# h-bridge_v3.net
KiCad netlist of a schematic drawn in EAGLE
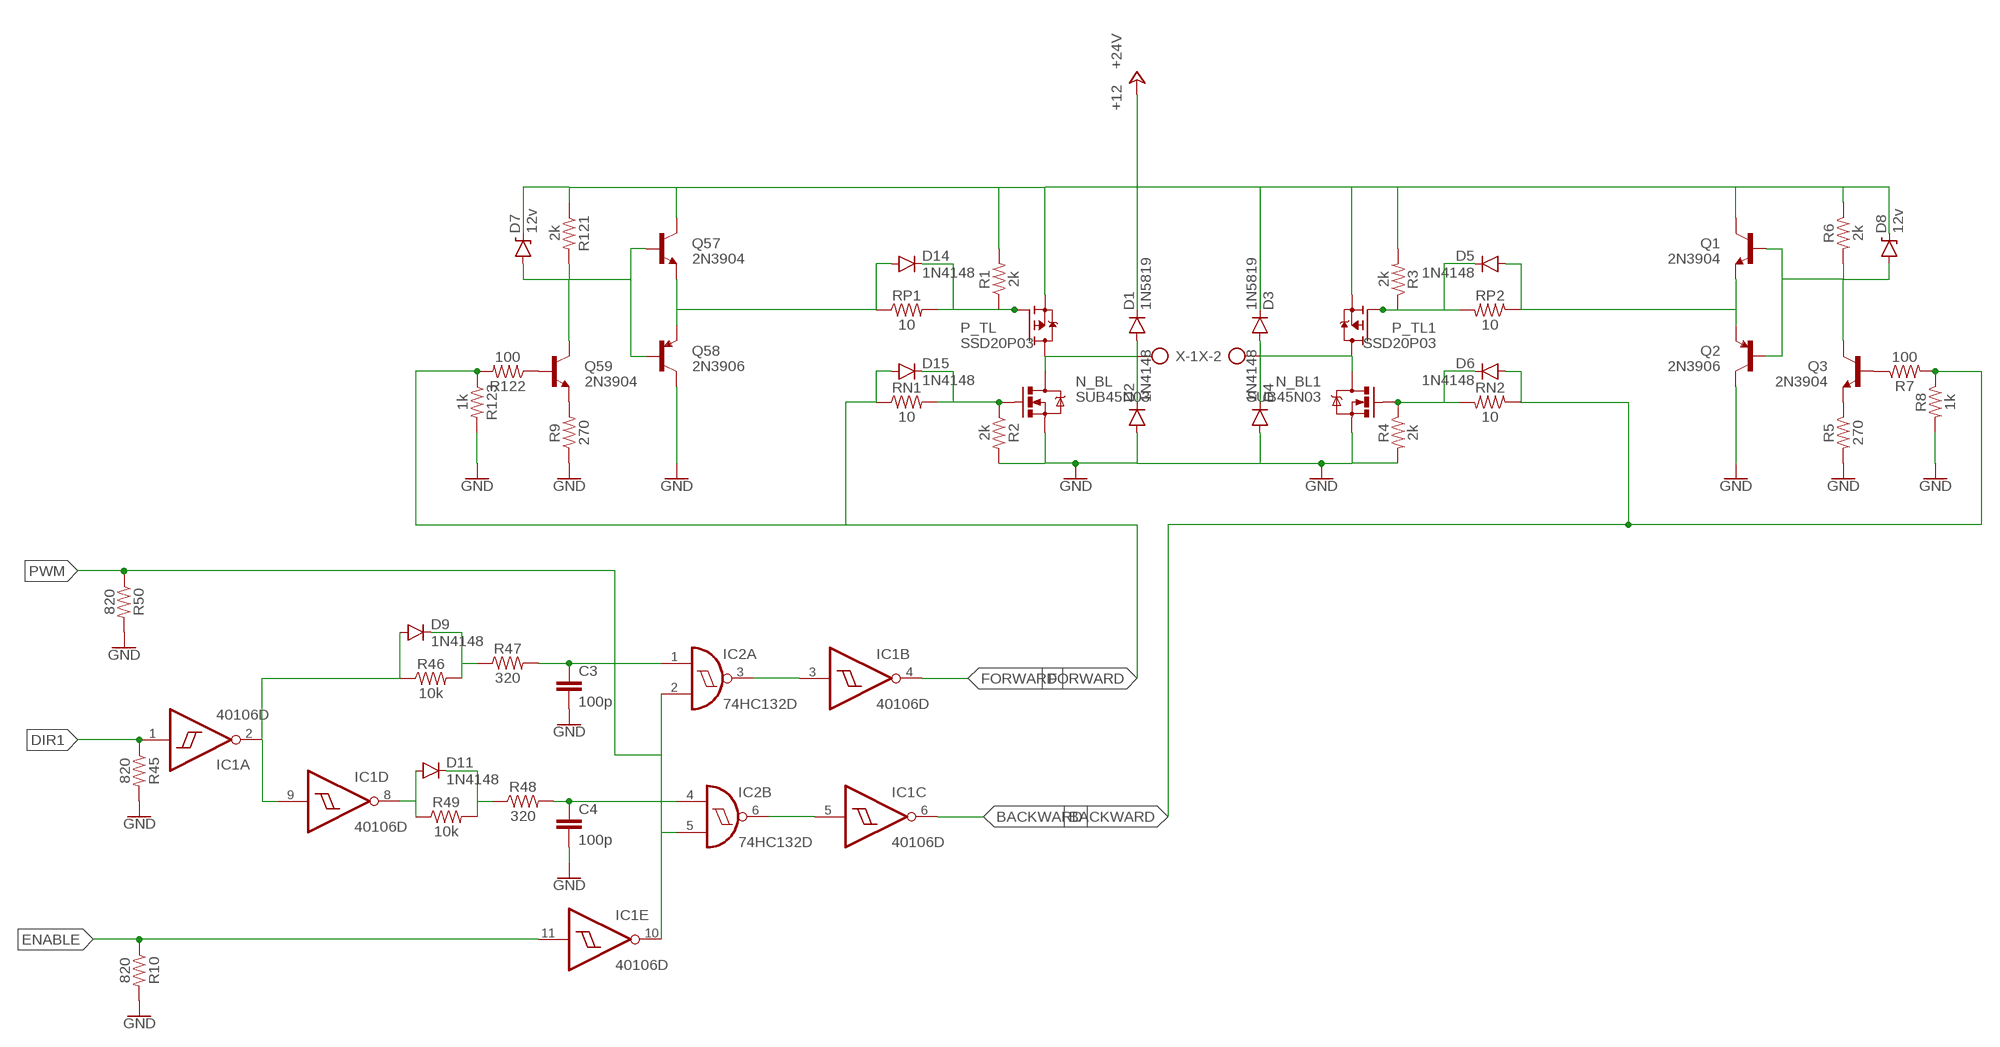
[diagram p0: schematic, sheet 1]

(export (version "E")
  (design (tool "Eeschema 10.0.6"))
  (components
    (comp (ref "C3")
      (value "100p")
      (footprint "eagle-import:0805-CAP")
      (libsource (lib "eagle-import") (part "1.0UF-25V-+80/-20(0805){dblquote}"))
    )
    (comp (ref "C4")
      (value "100p")
      (footprint "eagle-import:0805-CAP")
      (libsource (lib "eagle-import") (part "1.0UF-25V-+80/-20(0805){dblquote}"))
    )
    (comp (ref "D1")
      (value "1N5819")
      (footprint "eagle-import:SOD-123")
      (libsource (lib "eagle-import") (part "DIODESOD123"))
    )
    (comp (ref "D2")
      (value "1N4148")
      (footprint "eagle-import:SOD-123")
      (libsource (lib "eagle-import") (part "DIODESOD123"))
    )
    (comp (ref "D3")
      (value "1N5819")
      (footprint "eagle-import:SOD-123")
      (libsource (lib "eagle-import") (part "DIODESOD123"))
    )
    (comp (ref "D4")
      (value "1N4148")
      (footprint "eagle-import:SOD-123")
      (libsource (lib "eagle-import") (part "DIODESOD123"))
    )
    (comp (ref "D5")
      (value "1N4148")
      (footprint "eagle-import:SOD-123")
      (libsource (lib "eagle-import") (part "DIODESOD123"))
    )
    (comp (ref "D6")
      (value "1N4148")
      (footprint "eagle-import:SOD-123")
      (libsource (lib "eagle-import") (part "DIODESOD123"))
    )
    (comp (ref "D7")
      (value "12v")
      (footprint "eagle-import:SOD-123")
      (libsource (lib "eagle-import") (part "DIODE-ZENER16V"))
    )
    (comp (ref "D8")
      (value "12v")
      (footprint "eagle-import:SOD-123")
      (libsource (lib "eagle-import") (part "DIODE-ZENER16V"))
    )
    (comp (ref "D9")
      (value "1N4148")
      (footprint "eagle-import:SOD-123")
      (libsource (lib "eagle-import") (part "DIODESOD123"))
    )
    (comp (ref "D11")
      (value "1N4148")
      (footprint "eagle-import:SOD-123")
      (libsource (lib "eagle-import") (part "DIODESOD123"))
    )
    (comp (ref "D14")
      (value "1N4148")
      (footprint "eagle-import:SOD-123")
      (libsource (lib "eagle-import") (part "DIODESOD123"))
    )
    (comp (ref "D15")
      (value "1N4148")
      (footprint "eagle-import:SOD-123")
      (libsource (lib "eagle-import") (part "DIODESOD123"))
    )
    (comp (ref "IC1")
      (value "40106D")
      (footprint "eagle-import:SO14")
      (libsource (lib "eagle-import") (part "40106D"))
    )
    (comp (ref "IC2")
      (value "74HC132D")
      (footprint "eagle-import:SO14")
      (libsource (lib "eagle-import") (part "74132DHC"))
    )
    (comp (ref "N_BL")
      (value "SUB45N03")
      (footprint "eagle-import:TO-263_D2PAK")
      (libsource (lib "eagle-import") (part "MOSFET-NCHANNELPSMN7R0"))
    )
    (comp (ref "N_BL1")
      (value "SUB45N03")
      (footprint "eagle-import:TO-263_D2PAK")
      (libsource (lib "eagle-import") (part "MOSFET-NCHANNELPSMN7R0"))
    )
    (comp (ref "P_TL")
      (value "SSD20P03")
      (footprint "eagle-import:TO252")
      (libsource (lib "eagle-import") (part "FDD4141TO252"))
    )
    (comp (ref "P_TL1")
      (value "SSD20P03")
      (footprint "eagle-import:TO252")
      (libsource (lib "eagle-import") (part "FDD4141TO252"))
    )
    (comp (ref "Q1")
      (value "2N3904")
      (footprint "eagle-import:SOT23-3")
      (libsource (lib "eagle-import") (part "TRANSISTOR_NPNMMBT5088"))
    )
    (comp (ref "Q2")
      (value "2N3906")
      (footprint "eagle-import:SOT23-3")
      (libsource (lib "eagle-import") (part "TRANSISTOR_PNPPMBT3906"))
    )
    (comp (ref "Q3")
      (value "2N3904")
      (footprint "eagle-import:SOT23-3")
      (libsource (lib "eagle-import") (part "TRANSISTOR_NPNMMBT5088"))
    )
    (comp (ref "Q57")
      (value "2N3904")
      (footprint "eagle-import:SOT23-3")
      (libsource (lib "eagle-import") (part "TRANSISTOR_NPNMMBT5088"))
    )
    (comp (ref "Q58")
      (value "2N3906")
      (footprint "eagle-import:SOT23-3")
      (libsource (lib "eagle-import") (part "TRANSISTOR_PNPPMBT3906"))
    )
    (comp (ref "Q59")
      (value "2N3904")
      (footprint "eagle-import:SOT23-3")
      (libsource (lib "eagle-import") (part "TRANSISTOR_NPNMMBT5088"))
    )
    (comp (ref "R1")
      (value "2k")
      (footprint "eagle-import:AXIAL-0.3")
      (libsource (lib "eagle-import") (part "RESISTORAXIAL-0.3"))
    )
    (comp (ref "R2")
      (value "2k")
      (footprint "eagle-import:AXIAL-0.3")
      (libsource (lib "eagle-import") (part "RESISTORAXIAL-0.3"))
    )
    (comp (ref "R3")
      (value "2k")
      (footprint "eagle-import:AXIAL-0.3")
      (libsource (lib "eagle-import") (part "RESISTORAXIAL-0.3"))
    )
    (comp (ref "R4")
      (value "2k")
      (footprint "eagle-import:AXIAL-0.3")
      (libsource (lib "eagle-import") (part "RESISTORAXIAL-0.3"))
    )
    (comp (ref "R5")
      (value "270")
      (footprint "eagle-import:AXIAL-0.3")
      (libsource (lib "eagle-import") (part "RESISTORAXIAL-0.3"))
    )
    (comp (ref "R6")
      (value "2k")
      (footprint "eagle-import:AXIAL-0.3")
      (libsource (lib "eagle-import") (part "RESISTORAXIAL-0.3"))
    )
    (comp (ref "R7")
      (value "100")
      (footprint "eagle-import:AXIAL-0.3")
      (libsource (lib "eagle-import") (part "RESISTORAXIAL-0.3"))
    )
    (comp (ref "R8")
      (value "1k")
      (footprint "eagle-import:AXIAL-0.3")
      (libsource (lib "eagle-import") (part "RESISTORAXIAL-0.3"))
    )
    (comp (ref "R9")
      (value "270")
      (footprint "eagle-import:AXIAL-0.3")
      (libsource (lib "eagle-import") (part "RESISTORAXIAL-0.3"))
    )
    (comp (ref "R10")
      (value "820")
      (footprint "eagle-import:AXIAL-0.3")
      (libsource (lib "eagle-import") (part "RESISTORAXIAL-0.3"))
    )
    (comp (ref "R45")
      (value "820")
      (footprint "eagle-import:AXIAL-0.3")
      (libsource (lib "eagle-import") (part "RESISTORAXIAL-0.3"))
    )
    (comp (ref "R46")
      (value "10k")
      (footprint "eagle-import:AXIAL-0.3")
      (libsource (lib "eagle-import") (part "RESISTORAXIAL-0.3"))
    )
    (comp (ref "R47")
      (value "320")
      (footprint "eagle-import:AXIAL-0.3")
      (libsource (lib "eagle-import") (part "RESISTORAXIAL-0.3"))
    )
    (comp (ref "R48")
      (value "320")
      (footprint "eagle-import:AXIAL-0.3")
      (libsource (lib "eagle-import") (part "RESISTORAXIAL-0.3"))
    )
    (comp (ref "R49")
      (value "10k")
      (footprint "eagle-import:AXIAL-0.3")
      (libsource (lib "eagle-import") (part "RESISTORAXIAL-0.3"))
    )
    (comp (ref "R50")
      (value "820")
      (footprint "eagle-import:AXIAL-0.3")
      (libsource (lib "eagle-import") (part "RESISTORAXIAL-0.3"))
    )
    (comp (ref "R121")
      (value "2k")
      (footprint "eagle-import:AXIAL-0.3")
      (libsource (lib "eagle-import") (part "RESISTORAXIAL-0.3"))
    )
    (comp (ref "R122")
      (value "100")
      (footprint "eagle-import:AXIAL-0.3")
      (libsource (lib "eagle-import") (part "RESISTORAXIAL-0.3"))
    )
    (comp (ref "R123")
      (value "1k")
      (footprint "eagle-import:AXIAL-0.3")
      (libsource (lib "eagle-import") (part "RESISTORAXIAL-0.3"))
    )
    (comp (ref "RN1")
      (value "10")
      (footprint "eagle-import:AXIAL-0.3")
      (libsource (lib "eagle-import") (part "RESISTORAXIAL-0.3"))
    )
    (comp (ref "RN2")
      (value "10")
      (footprint "eagle-import:AXIAL-0.3")
      (libsource (lib "eagle-import") (part "RESISTORAXIAL-0.3"))
    )
    (comp (ref "RP1")
      (value "10")
      (footprint "eagle-import:AXIAL-0.3")
      (libsource (lib "eagle-import") (part "RESISTORAXIAL-0.3"))
    )
    (comp (ref "RP2")
      (value "10")
      (footprint "eagle-import:AXIAL-0.3")
      (libsource (lib "eagle-import") (part "RESISTORAXIAL-0.3"))
    )
    (comp (ref "X")
      (value "SMKDSP_1,5/2")
      (footprint "eagle-import:SMKDSP_1,5_2")
      (fields (field (name "MF") "FARNELL") (field (name "MPN") "1733570"))
      (libsource (lib "eagle-import") (part "SMKDSP_1,5/2"))
    )
  )
  (nets
    (net (code "1") (name "+12    +24V") (class "Default")
      (node (ref "D1") (pin "C") (pinfunction "C_C") (pintype "passive"))
      (node (ref "D3") (pin "C") (pinfunction "C_C") (pintype "passive"))
      (node (ref "D7") (pin "C") (pinfunction "C_C") (pintype "passive"))
      (node (ref "D8") (pin "C") (pinfunction "C_C") (pintype "passive"))
      (node (ref "P_TL") (pin "2") (pinfunction "S_2") (pintype "passive"))
      (node (ref "P_TL1") (pin "2") (pinfunction "S_2") (pintype "passive"))
      (node (ref "Q1") (pin "3") (pinfunction "C_3") (pintype "passive"))
      (node (ref "Q57") (pin "3") (pinfunction "C_3") (pintype "passive"))
      (node (ref "R1") (pin "P$2") (pinfunction "2_P$2") (pintype "passive"))
      (node (ref "R121") (pin "P$1") (pinfunction "1_P$1") (pintype "passive"))
      (node (ref "R3") (pin "P$2") (pinfunction "2_P$2") (pintype "passive"))
      (node (ref "R6") (pin "P$1") (pinfunction "1_P$1") (pintype "passive"))
    )
    (net (code "2") (name "BACKWARD") (class "Default")
      (node (ref "D6") (pin "A") (pinfunction "A_A") (pintype "passive"))
      (node (ref "IC1") (pin "6") (pinfunction "O_6") (pintype "output"))
      (node (ref "R7") (pin "P$2") (pinfunction "2_P$2") (pintype "passive"))
      (node (ref "R8") (pin "P$1") (pinfunction "1_P$1") (pintype "passive"))
      (node (ref "RN2") (pin "P$1") (pinfunction "1_P$1") (pintype "passive"))
    )
    (net (code "3") (name "DIR1") (class "Default")
      (node (ref "IC1") (pin "1") (pinfunction "I_1") (pintype "input"))
      (node (ref "R45") (pin "P$1") (pinfunction "1_P$1") (pintype "passive"))
    )
    (net (code "4") (name "ENABLE") (class "Default")
      (node (ref "IC1") (pin "11") (pinfunction "I_11") (pintype "input"))
      (node (ref "R10") (pin "P$1") (pinfunction "1_P$1") (pintype "passive"))
    )
    (net (code "5") (name "FORWARD") (class "Default")
      (node (ref "D15") (pin "A") (pinfunction "A_A") (pintype "passive"))
      (node (ref "IC1") (pin "4") (pinfunction "O_4") (pintype "output"))
      (node (ref "R122") (pin "P$2") (pinfunction "2_P$2") (pintype "passive"))
      (node (ref "R123") (pin "P$1") (pinfunction "1_P$1") (pintype "passive"))
      (node (ref "RN1") (pin "P$1") (pinfunction "1_P$1") (pintype "passive"))
    )
    (net (code "6") (name "GND") (class "Default")
      (node (ref "C3") (pin "2") (pinfunction "2_2") (pintype "passive"))
      (node (ref "C4") (pin "2") (pinfunction "2_2") (pintype "passive"))
      (node (ref "D2") (pin "A") (pinfunction "A_A") (pintype "passive"))
      (node (ref "D4") (pin "A") (pinfunction "A_A") (pintype "passive"))
      (node (ref "N_BL") (pin "3") (pinfunction "S_3") (pintype "passive"))
      (node (ref "N_BL1") (pin "3") (pinfunction "S_3") (pintype "passive"))
      (node (ref "Q2") (pin "3") (pinfunction "C_3") (pintype "passive"))
      (node (ref "Q58") (pin "3") (pinfunction "C_3") (pintype "passive"))
      (node (ref "R10") (pin "P$2") (pinfunction "2_P$2") (pintype "passive"))
      (node (ref "R123") (pin "P$2") (pinfunction "2_P$2") (pintype "passive"))
      (node (ref "R2") (pin "P$2") (pinfunction "2_P$2") (pintype "passive"))
      (node (ref "R4") (pin "P$2") (pinfunction "2_P$2") (pintype "passive"))
      (node (ref "R45") (pin "P$2") (pinfunction "2_P$2") (pintype "passive"))
      (node (ref "R5") (pin "P$2") (pinfunction "2_P$2") (pintype "passive"))
      (node (ref "R50") (pin "P$2") (pinfunction "2_P$2") (pintype "passive"))
      (node (ref "R8") (pin "P$2") (pinfunction "2_P$2") (pintype "passive"))
      (node (ref "R9") (pin "P$1") (pinfunction "1_P$1") (pintype "passive"))
    )
    (net (code "7") (name "Net-(IC1A-O)") (class "Default")
      (node (ref "D9") (pin "A") (pinfunction "A_A") (pintype "passive"))
      (node (ref "IC1") (pin "2") (pinfunction "O_2") (pintype "output"))
      (node (ref "IC1") (pin "9") (pinfunction "I_9") (pintype "input"))
      (node (ref "R46") (pin "P$1") (pinfunction "1_P$1") (pintype "passive"))
    )
    (net (code "8") (name "Net-(IC1B-I)") (class "Default")
      (node (ref "IC1") (pin "3") (pinfunction "I_3") (pintype "input"))
      (node (ref "IC2") (pin "3") (pinfunction "O_3") (pintype "output"))
    )
    (net (code "9") (name "Net-(IC1C-I)") (class "Default")
      (node (ref "IC1") (pin "5") (pinfunction "I_5") (pintype "input"))
      (node (ref "IC2") (pin "6") (pinfunction "O_6") (pintype "output"))
    )
    (net (code "10") (name "Net-(IC1D-O)") (class "Default")
      (node (ref "D11") (pin "A") (pinfunction "A_A") (pintype "passive"))
      (node (ref "IC1") (pin "8") (pinfunction "O_8") (pintype "output"))
      (node (ref "R49") (pin "P$1") (pinfunction "1_P$1") (pintype "passive"))
    )
    (net (code "11") (name "Net-(IC2A-I0)") (class "Default")
      (node (ref "C3") (pin "1") (pinfunction "1_1") (pintype "passive"))
      (node (ref "IC2") (pin "1") (pinfunction "I0_1") (pintype "input"))
      (node (ref "R47") (pin "P$2") (pinfunction "2_P$2") (pintype "passive"))
    )
    (net (code "12") (name "Net-(IC2B-I0)") (class "Default")
      (node (ref "C4") (pin "1") (pinfunction "1_1") (pintype "passive"))
      (node (ref "IC2") (pin "4") (pinfunction "I0_4") (pintype "input"))
      (node (ref "R48") (pin "P$2") (pinfunction "2_P$2") (pintype "passive"))
    )
    (net (code "13") (name "Net-(N_BL-D)") (class "Default")
      (node (ref "D1") (pin "A") (pinfunction "A_A") (pintype "passive"))
      (node (ref "D2") (pin "C") (pinfunction "C_C") (pintype "passive"))
      (node (ref "N_BL") (pin "2") (pinfunction "D_2") (pintype "passive"))
      (node (ref "P_TL") (pin "3") (pinfunction "D_3") (pintype "passive"))
      (node (ref "X") (pin "1") (pinfunction "KL_1") (pintype "passive"))
    )
    (net (code "14") (name "Net-(N_BL-G)") (class "Default")
      (node (ref "D15") (pin "C") (pinfunction "C_C") (pintype "passive"))
      (node (ref "N_BL") (pin "1") (pinfunction "G_1") (pintype "passive"))
      (node (ref "R2") (pin "P$1") (pinfunction "1_P$1") (pintype "passive"))
      (node (ref "RN1") (pin "P$2") (pinfunction "2_P$2") (pintype "passive"))
    )
    (net (code "15") (name "Net-(N_BL1-D)") (class "Default")
      (node (ref "D3") (pin "A") (pinfunction "A_A") (pintype "passive"))
      (node (ref "D4") (pin "C") (pinfunction "C_C") (pintype "passive"))
      (node (ref "N_BL1") (pin "2") (pinfunction "D_2") (pintype "passive"))
      (node (ref "P_TL1") (pin "3") (pinfunction "D_3") (pintype "passive"))
      (node (ref "X") (pin "2") (pinfunction "KL_2") (pintype "passive"))
    )
    (net (code "16") (name "Net-(N_BL1-G)") (class "Default")
      (node (ref "D6") (pin "C") (pinfunction "C_C") (pintype "passive"))
      (node (ref "N_BL1") (pin "1") (pinfunction "G_1") (pintype "passive"))
      (node (ref "R4") (pin "P$1") (pinfunction "1_P$1") (pintype "passive"))
      (node (ref "RN2") (pin "P$2") (pinfunction "2_P$2") (pintype "passive"))
    )
    (net (code "17") (name "Net-(P_TL-G)") (class "Default")
      (node (ref "D14") (pin "C") (pinfunction "C_C") (pintype "passive"))
      (node (ref "P_TL") (pin "1") (pinfunction "G_1") (pintype "passive"))
      (node (ref "R1") (pin "P$1") (pinfunction "1_P$1") (pintype "passive"))
      (node (ref "RP1") (pin "P$2") (pinfunction "2_P$2") (pintype "passive"))
    )
    (net (code "18") (name "Net-(P_TL1-G)") (class "Default")
      (node (ref "D5") (pin "C") (pinfunction "C_C") (pintype "passive"))
      (node (ref "P_TL1") (pin "1") (pinfunction "G_1") (pintype "passive"))
      (node (ref "R3") (pin "P$1") (pinfunction "1_P$1") (pintype "passive"))
      (node (ref "RP2") (pin "P$2") (pinfunction "2_P$2") (pintype "passive"))
    )
    (net (code "19") (name "Net-(Q1-B)") (class "Default")
      (node (ref "D8") (pin "A") (pinfunction "A_A") (pintype "passive"))
      (node (ref "Q1") (pin "1") (pinfunction "B_1") (pintype "passive"))
      (node (ref "Q2") (pin "1") (pinfunction "B_1") (pintype "passive"))
      (node (ref "Q3") (pin "3") (pinfunction "C_3") (pintype "passive"))
      (node (ref "R6") (pin "P$2") (pinfunction "2_P$2") (pintype "passive"))
    )
    (net (code "20") (name "Net-(Q1-E)") (class "Default")
      (node (ref "D5") (pin "A") (pinfunction "A_A") (pintype "passive"))
      (node (ref "Q1") (pin "2") (pinfunction "E_2") (pintype "passive"))
      (node (ref "Q2") (pin "2") (pinfunction "E_2") (pintype "passive"))
      (node (ref "RP2") (pin "P$1") (pinfunction "1_P$1") (pintype "passive"))
    )
    (net (code "21") (name "Net-(Q3-B)") (class "Default")
      (node (ref "Q3") (pin "1") (pinfunction "B_1") (pintype "passive"))
      (node (ref "R7") (pin "P$1") (pinfunction "1_P$1") (pintype "passive"))
    )
    (net (code "22") (name "Net-(Q3-E)") (class "Default")
      (node (ref "Q3") (pin "2") (pinfunction "E_2") (pintype "passive"))
      (node (ref "R5") (pin "P$1") (pinfunction "1_P$1") (pintype "passive"))
    )
    (net (code "23") (name "Net-(Q57-B)") (class "Default")
      (node (ref "D7") (pin "A") (pinfunction "A_A") (pintype "passive"))
      (node (ref "Q57") (pin "1") (pinfunction "B_1") (pintype "passive"))
      (node (ref "Q58") (pin "1") (pinfunction "B_1") (pintype "passive"))
      (node (ref "Q59") (pin "3") (pinfunction "C_3") (pintype "passive"))
      (node (ref "R121") (pin "P$2") (pinfunction "2_P$2") (pintype "passive"))
    )
    (net (code "24") (name "Net-(Q57-E)") (class "Default")
      (node (ref "D14") (pin "A") (pinfunction "A_A") (pintype "passive"))
      (node (ref "Q57") (pin "2") (pinfunction "E_2") (pintype "passive"))
      (node (ref "Q58") (pin "2") (pinfunction "E_2") (pintype "passive"))
      (node (ref "RP1") (pin "P$1") (pinfunction "1_P$1") (pintype "passive"))
    )
    (net (code "25") (name "Net-(Q59-B)") (class "Default")
      (node (ref "Q59") (pin "1") (pinfunction "B_1") (pintype "passive"))
      (node (ref "R122") (pin "P$1") (pinfunction "1_P$1") (pintype "passive"))
    )
    (net (code "26") (name "Net-(Q59-E)") (class "Default")
      (node (ref "Q59") (pin "2") (pinfunction "E_2") (pintype "passive"))
      (node (ref "R9") (pin "P$2") (pinfunction "2_P$2") (pintype "passive"))
    )
    (net (code "27") (name "Net-(R46-2)") (class "Default")
      (node (ref "D9") (pin "C") (pinfunction "C_C") (pintype "passive"))
      (node (ref "R46") (pin "P$2") (pinfunction "2_P$2") (pintype "passive"))
      (node (ref "R47") (pin "P$1") (pinfunction "1_P$1") (pintype "passive"))
    )
    (net (code "28") (name "Net-(R48-1)") (class "Default")
      (node (ref "D11") (pin "C") (pinfunction "C_C") (pintype "passive"))
      (node (ref "R48") (pin "P$1") (pinfunction "1_P$1") (pintype "passive"))
      (node (ref "R49") (pin "P$2") (pinfunction "2_P$2") (pintype "passive"))
    )
    (net (code "29") (name "PWM") (class "Default")
      (node (ref "IC1") (pin "10") (pinfunction "O_10") (pintype "output"))
      (node (ref "IC2") (pin "2") (pinfunction "I1_2") (pintype "input"))
      (node (ref "IC2") (pin "5") (pinfunction "I1_5") (pintype "input"))
      (node (ref "R50") (pin "P$1") (pinfunction "1_P$1") (pintype "passive"))
    )
  )
)
